# 1z16_7seg-eagle.net
KiCad netlist of a schematic drawn in EAGLE
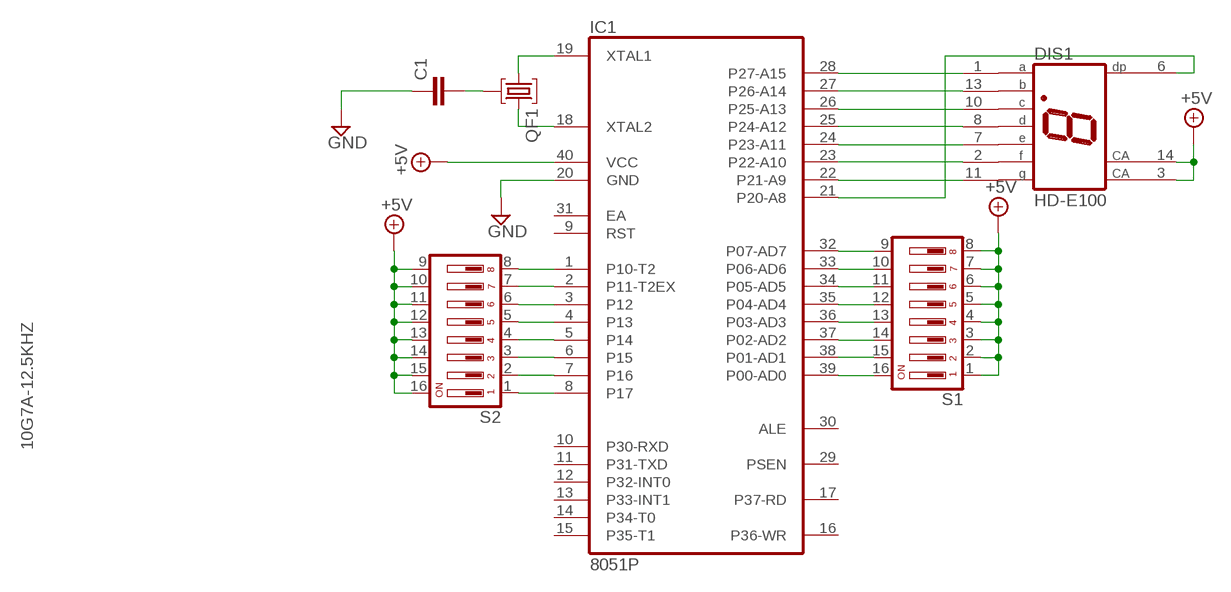
[diagram p0: schematic, sheet 1]

(export (version "E")
  (design (tool "Eeschema 10.0.6"))
  (components
    (comp (ref "C1")
      (value "C2,5-3")
      (footprint "eagle-import:C2.5-3")
      (libsource (lib "eagle-import") (part "C2,5-3"))
    )
    (comp (ref "DIS1")
      (value "HD-E100")
      (footprint "eagle-import:HDSP-I")
      (libsource (lib "eagle-import") (part "HD-E100"))
    )
    (comp (ref "IC1")
      (value "8051P")
      (footprint "eagle-import:DIL40")
      (libsource (lib "eagle-import") (part "8051P"))
    )
    (comp (ref "QF1")
      (value "10G7A-12.5KHZ")
      (footprint "eagle-import:HC49U")
      (libsource (lib "eagle-import") (part "10G7A-12.5KHZ"))
    )
    (comp (ref "S1")
      (value "DA08")
      (footprint "eagle-import:DA-08")
      (fields (field (name "MPN") "MCDA08"))
      (libsource (lib "eagle-import") (part "DA08"))
    )
    (comp (ref "S2")
      (value "DA08")
      (footprint "eagle-import:DA-08")
      (fields (field (name "MPN") "MCDA08"))
      (libsource (lib "eagle-import") (part "DA08"))
    )
  )
  (nets
    (net (code "1") (name "+5V") (class "Default")
      (node (ref "DIS1") (pin "14") (pinfunction "CA_14") (pintype "passive"))
      (node (ref "DIS1") (pin "3") (pinfunction "CA_3") (pintype "passive"))
      (node (ref "IC1") (pin "40") (pinfunction "VCC_40") (pintype "power_in"))
      (node (ref "S1") (pin "1") (pinfunction "1_1") (pintype "passive"))
      (node (ref "S1") (pin "2") (pinfunction "2_2") (pintype "passive"))
      (node (ref "S1") (pin "3") (pinfunction "3_3") (pintype "passive"))
      (node (ref "S1") (pin "4") (pinfunction "4_4") (pintype "passive"))
      (node (ref "S1") (pin "5") (pinfunction "5_5") (pintype "passive"))
      (node (ref "S1") (pin "6") (pinfunction "6_6") (pintype "passive"))
      (node (ref "S1") (pin "7") (pinfunction "7_7") (pintype "passive"))
      (node (ref "S1") (pin "8") (pinfunction "8_8") (pintype "passive"))
      (node (ref "S2") (pin "10") (pinfunction "10_10") (pintype "passive"))
      (node (ref "S2") (pin "11") (pinfunction "11_11") (pintype "passive"))
      (node (ref "S2") (pin "12") (pinfunction "12_12") (pintype "passive"))
      (node (ref "S2") (pin "13") (pinfunction "13_13") (pintype "passive"))
      (node (ref "S2") (pin "14") (pinfunction "14_14") (pintype "passive"))
      (node (ref "S2") (pin "15") (pinfunction "15_15") (pintype "passive"))
      (node (ref "S2") (pin "16") (pinfunction "16_16") (pintype "passive"))
      (node (ref "S2") (pin "9") (pinfunction "9_9") (pintype "passive"))
    )
    (net (code "2") (name "GND") (class "Default")
      (node (ref "C1") (pin "1") (pinfunction "1_1") (pintype "passive"))
      (node (ref "IC1") (pin "20") (pinfunction "GND_20") (pintype "power_in"))
    )
    (net (code "3") (name "Net-(C1-Pad2)") (class "Default")
      (node (ref "C1") (pin "2") (pinfunction "2_2") (pintype "passive"))
      (node (ref "QF1") (pin "2") (pinfunction "2_2") (pintype "passive"))
    )
    (net (code "4") (name "Net-(DIS1-A)") (class "Default")
      (node (ref "DIS1") (pin "1") (pinfunction "A_1") (pintype "passive"))
      (node (ref "IC1") (pin "28") (pinfunction "P27-A15_28") (pintype "bidirectional"))
    )
    (net (code "5") (name "Net-(DIS1-B)") (class "Default")
      (node (ref "DIS1") (pin "13") (pinfunction "B_13") (pintype "passive"))
      (node (ref "IC1") (pin "27") (pinfunction "P26-A14_27") (pintype "bidirectional"))
    )
    (net (code "6") (name "Net-(DIS1-C)") (class "Default")
      (node (ref "DIS1") (pin "10") (pinfunction "C_10") (pintype "passive"))
      (node (ref "IC1") (pin "26") (pinfunction "P25-A13_26") (pintype "bidirectional"))
    )
    (net (code "7") (name "Net-(DIS1-D)") (class "Default")
      (node (ref "DIS1") (pin "8") (pinfunction "D_8") (pintype "passive"))
      (node (ref "IC1") (pin "25") (pinfunction "P24-A12_25") (pintype "bidirectional"))
    )
    (net (code "8") (name "Net-(DIS1-DP)") (class "Default")
      (node (ref "DIS1") (pin "6") (pinfunction "DP_6") (pintype "passive"))
      (node (ref "IC1") (pin "21") (pinfunction "P20-A8_21") (pintype "bidirectional"))
    )
    (net (code "9") (name "Net-(DIS1-E)") (class "Default")
      (node (ref "DIS1") (pin "7") (pinfunction "E_7") (pintype "passive"))
      (node (ref "IC1") (pin "24") (pinfunction "P23-A11_24") (pintype "bidirectional"))
    )
    (net (code "10") (name "Net-(DIS1-F)") (class "Default")
      (node (ref "DIS1") (pin "2") (pinfunction "F_2") (pintype "passive"))
      (node (ref "IC1") (pin "23") (pinfunction "P22-A10_23") (pintype "bidirectional"))
    )
    (net (code "11") (name "Net-(DIS1-G)") (class "Default")
      (node (ref "DIS1") (pin "11") (pinfunction "G_11") (pintype "passive"))
      (node (ref "IC1") (pin "22") (pinfunction "P21-A9_22") (pintype "bidirectional"))
    )
    (net (code "12") (name "Net-(IC1-P00-AD0)") (class "Default")
      (node (ref "IC1") (pin "39") (pinfunction "P00-AD0_39") (pintype "bidirectional"))
      (node (ref "S1") (pin "16") (pinfunction "16_16") (pintype "passive"))
    )
    (net (code "13") (name "Net-(IC1-P01-AD1)") (class "Default")
      (node (ref "IC1") (pin "38") (pinfunction "P01-AD1_38") (pintype "bidirectional"))
      (node (ref "S1") (pin "15") (pinfunction "15_15") (pintype "passive"))
    )
    (net (code "14") (name "Net-(IC1-P02-AD2)") (class "Default")
      (node (ref "IC1") (pin "37") (pinfunction "P02-AD2_37") (pintype "bidirectional"))
      (node (ref "S1") (pin "14") (pinfunction "14_14") (pintype "passive"))
    )
    (net (code "15") (name "Net-(IC1-P03-AD3)") (class "Default")
      (node (ref "IC1") (pin "36") (pinfunction "P03-AD3_36") (pintype "bidirectional"))
      (node (ref "S1") (pin "13") (pinfunction "13_13") (pintype "passive"))
    )
    (net (code "16") (name "Net-(IC1-P04-AD4)") (class "Default")
      (node (ref "IC1") (pin "35") (pinfunction "P04-AD4_35") (pintype "bidirectional"))
      (node (ref "S1") (pin "12") (pinfunction "12_12") (pintype "passive"))
    )
    (net (code "17") (name "Net-(IC1-P05-AD5)") (class "Default")
      (node (ref "IC1") (pin "34") (pinfunction "P05-AD5_34") (pintype "bidirectional"))
      (node (ref "S1") (pin "11") (pinfunction "11_11") (pintype "passive"))
    )
    (net (code "18") (name "Net-(IC1-P06-AD6)") (class "Default")
      (node (ref "IC1") (pin "33") (pinfunction "P06-AD6_33") (pintype "bidirectional"))
      (node (ref "S1") (pin "10") (pinfunction "10_10") (pintype "passive"))
    )
    (net (code "19") (name "Net-(IC1-P07-AD7)") (class "Default")
      (node (ref "IC1") (pin "32") (pinfunction "P07-AD7_32") (pintype "bidirectional"))
      (node (ref "S1") (pin "9") (pinfunction "9_9") (pintype "passive"))
    )
    (net (code "20") (name "Net-(IC1-P10-T2)") (class "Default")
      (node (ref "IC1") (pin "1") (pinfunction "P10-T2_1") (pintype "bidirectional"))
      (node (ref "S2") (pin "8") (pinfunction "8_8") (pintype "passive"))
    )
    (net (code "21") (name "Net-(IC1-P11-T2EX)") (class "Default")
      (node (ref "IC1") (pin "2") (pinfunction "P11-T2EX_2") (pintype "bidirectional"))
      (node (ref "S2") (pin "7") (pinfunction "7_7") (pintype "passive"))
    )
    (net (code "22") (name "Net-(IC1-P12)") (class "Default")
      (node (ref "IC1") (pin "3") (pinfunction "P12_3") (pintype "bidirectional"))
      (node (ref "S2") (pin "6") (pinfunction "6_6") (pintype "passive"))
    )
    (net (code "23") (name "Net-(IC1-P13)") (class "Default")
      (node (ref "IC1") (pin "4") (pinfunction "P13_4") (pintype "bidirectional"))
      (node (ref "S2") (pin "5") (pinfunction "5_5") (pintype "passive"))
    )
    (net (code "24") (name "Net-(IC1-P14)") (class "Default")
      (node (ref "IC1") (pin "5") (pinfunction "P14_5") (pintype "bidirectional"))
      (node (ref "S2") (pin "4") (pinfunction "4_4") (pintype "passive"))
    )
    (net (code "25") (name "Net-(IC1-P15)") (class "Default")
      (node (ref "IC1") (pin "6") (pinfunction "P15_6") (pintype "bidirectional"))
      (node (ref "S2") (pin "3") (pinfunction "3_3") (pintype "passive"))
    )
    (net (code "26") (name "Net-(IC1-P16)") (class "Default")
      (node (ref "IC1") (pin "7") (pinfunction "P16_7") (pintype "bidirectional"))
      (node (ref "S2") (pin "2") (pinfunction "2_2") (pintype "passive"))
    )
    (net (code "27") (name "Net-(IC1-P17)") (class "Default")
      (node (ref "IC1") (pin "8") (pinfunction "P17_8") (pintype "bidirectional"))
      (node (ref "S2") (pin "1") (pinfunction "1_1") (pintype "passive"))
    )
    (net (code "28") (name "Net-(IC1-XTAL1)") (class "Default")
      (node (ref "IC1") (pin "19") (pinfunction "XTAL1_19") (pintype "input"))
      (node (ref "QF1") (pin "1") (pinfunction "1_1") (pintype "passive"))
    )
    (net (code "29") (name "Net-(IC1-XTAL2)") (class "Default")
      (node (ref "IC1") (pin "18") (pinfunction "XTAL2_18") (pintype "input"))
      (node (ref "QF1") (pin "3") (pinfunction "3_3") (pintype "passive"))
    )
    (net (code "30") (name "unconnected-(IC1-ALE-Pad30)") (class "Default")
      (node (ref "IC1") (pin "30") (pinfunction "ALE_30") (pintype "output"))
    )
    (net (code "31") (name "unconnected-(IC1-EA-Pad31)") (class "Default")
      (node (ref "IC1") (pin "31") (pinfunction "EA_31") (pintype "input"))
    )
    (net (code "32") (name "unconnected-(IC1-P30-RXD-Pad10)") (class "Default")
      (node (ref "IC1") (pin "10") (pinfunction "P30-RXD_10") (pintype "bidirectional"))
    )
    (net (code "33") (name "unconnected-(IC1-P31-TXD-Pad11)") (class "Default")
      (node (ref "IC1") (pin "11") (pinfunction "P31-TXD_11") (pintype "bidirectional"))
    )
    (net (code "34") (name "unconnected-(IC1-P32-INT0-Pad12)") (class "Default")
      (node (ref "IC1") (pin "12") (pinfunction "P32-INT0_12") (pintype "bidirectional"))
    )
    (net (code "35") (name "unconnected-(IC1-P33-INT1-Pad13)") (class "Default")
      (node (ref "IC1") (pin "13") (pinfunction "P33-INT1_13") (pintype "bidirectional"))
    )
    (net (code "36") (name "unconnected-(IC1-P34-T0-Pad14)") (class "Default")
      (node (ref "IC1") (pin "14") (pinfunction "P34-T0_14") (pintype "bidirectional"))
    )
    (net (code "37") (name "unconnected-(IC1-P35-T1-Pad15)") (class "Default")
      (node (ref "IC1") (pin "15") (pinfunction "P35-T1_15") (pintype "bidirectional"))
    )
    (net (code "38") (name "unconnected-(IC1-P36-WR-Pad16)") (class "Default")
      (node (ref "IC1") (pin "16") (pinfunction "P36-WR_16") (pintype "bidirectional"))
    )
    (net (code "39") (name "unconnected-(IC1-P37-RD-Pad17)") (class "Default")
      (node (ref "IC1") (pin "17") (pinfunction "P37-RD_17") (pintype "bidirectional"))
    )
    (net (code "40") (name "unconnected-(IC1-PSEN-Pad29)") (class "Default")
      (node (ref "IC1") (pin "29") (pinfunction "PSEN_29") (pintype "output"))
    )
    (net (code "41") (name "unconnected-(IC1-RST-Pad9)") (class "Default")
      (node (ref "IC1") (pin "9") (pinfunction "RST_9") (pintype "input"))
    )
  )
)
